# MCU.net
KiCad netlist of a schematic drawn in Altium Designer
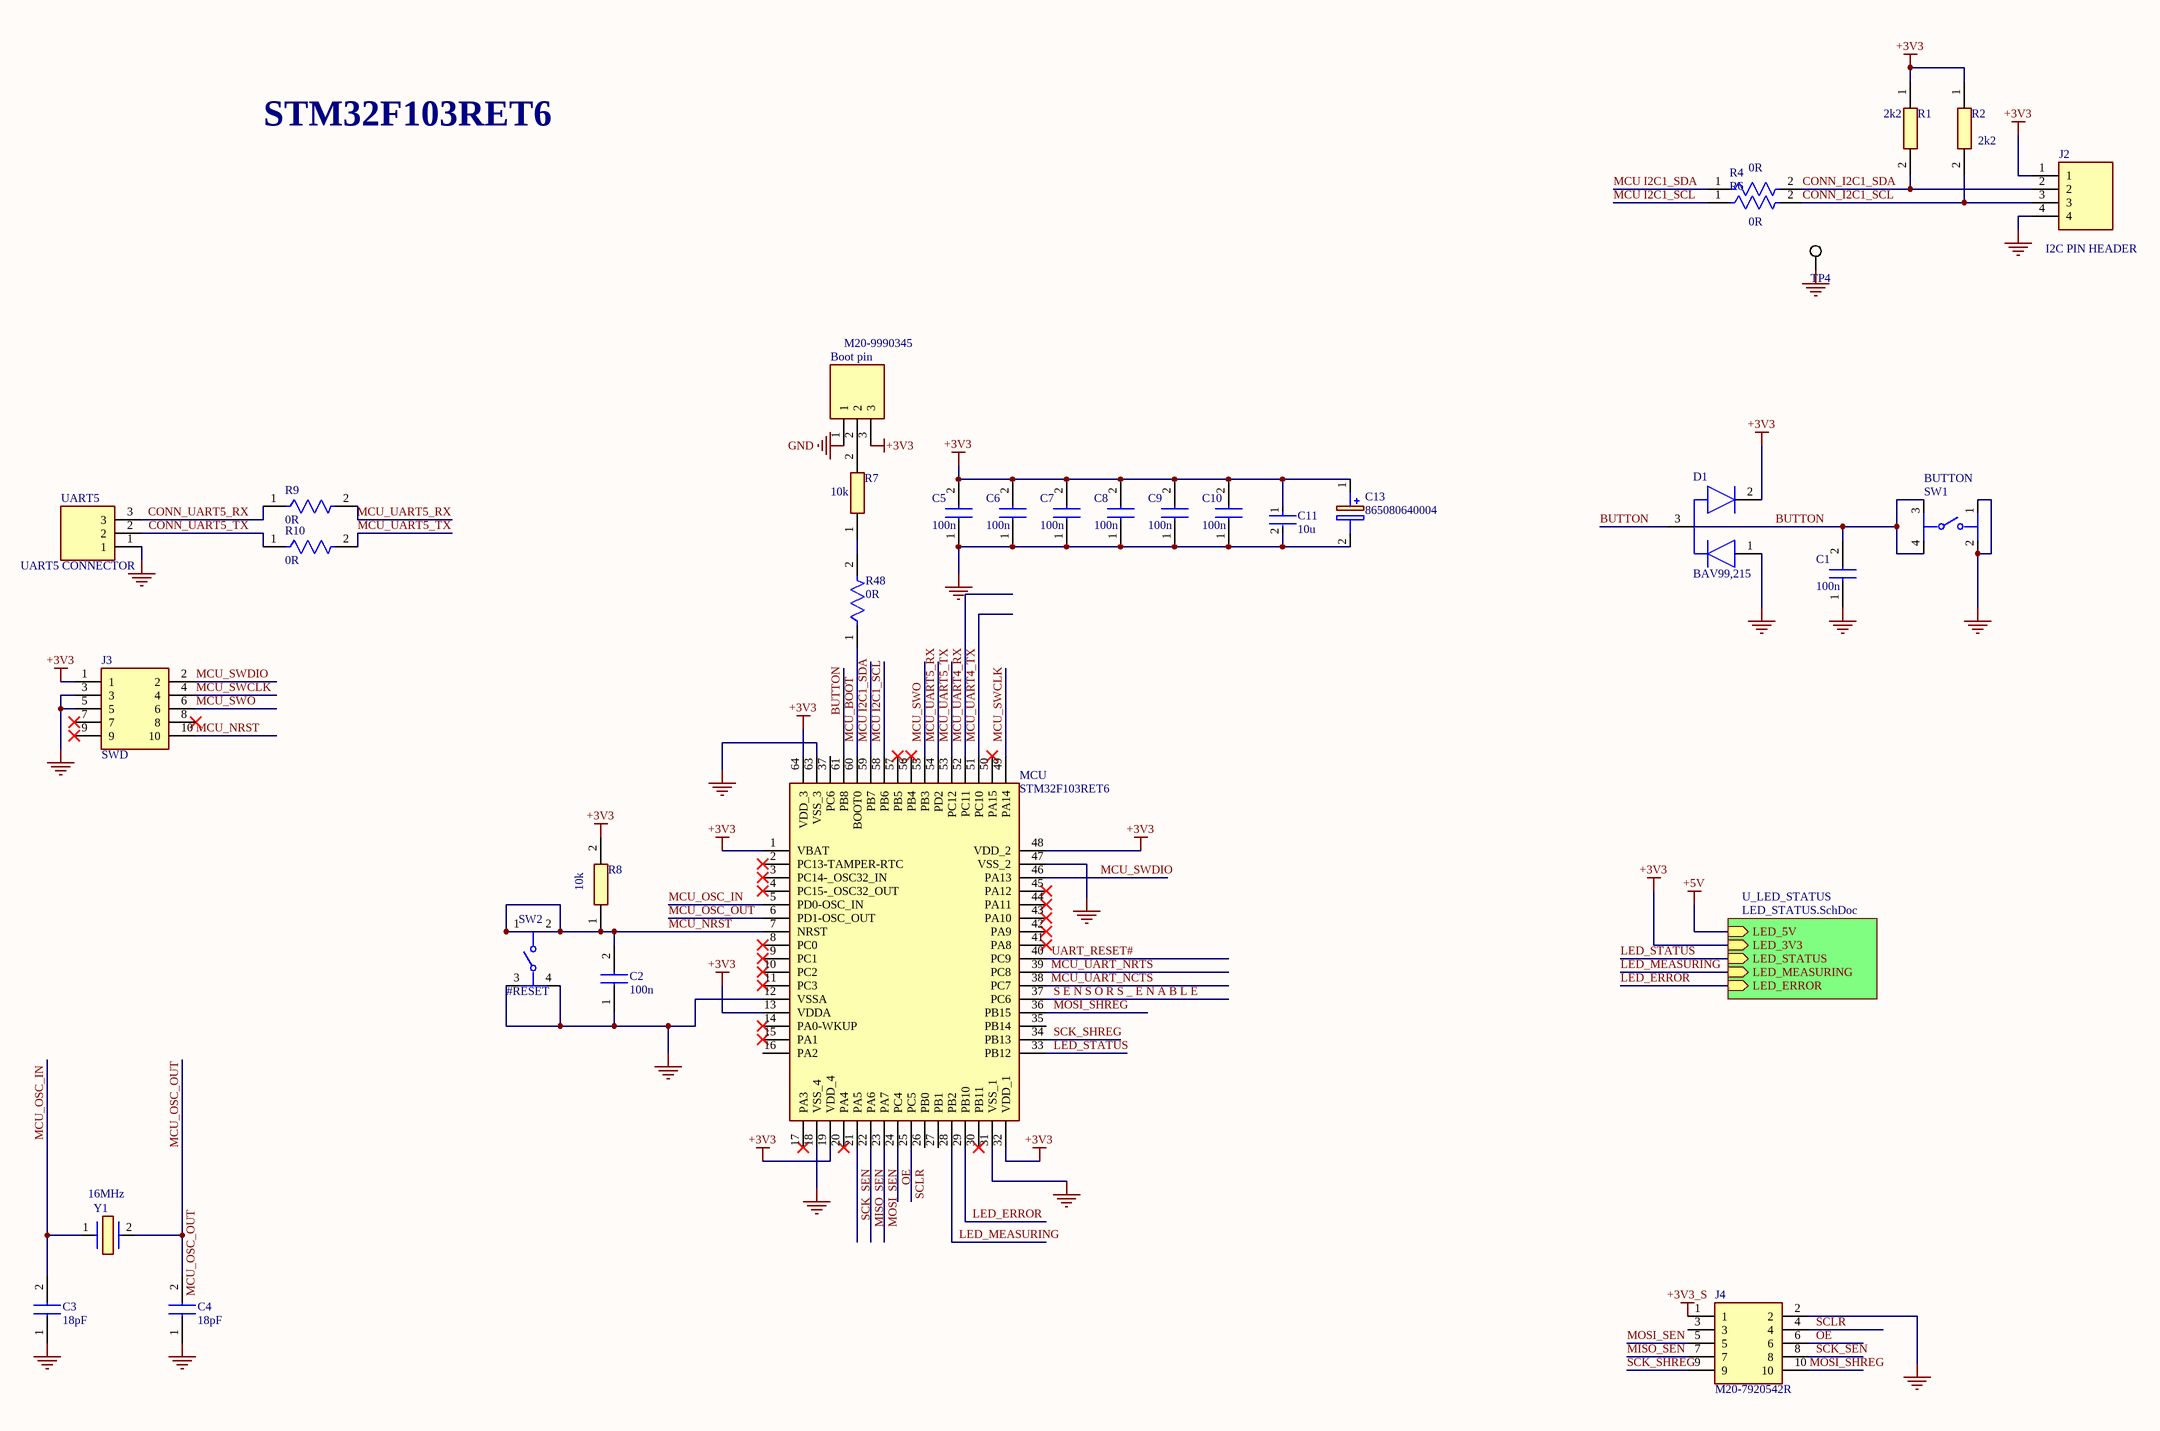
[diagram p0: MCU.SchDoc]

(export (version "E")
  (design (tool "Eeschema 10.0.6"))
  (components
    (comp (ref "Boot pin")
      (value "M20-9990345")
      (footprint "SamacSys:HDRV3W64P0X254_1X3_762X254X864P")
      (description "Connector")
      (fields (field (name "MOUSER PART NUMBER") "855-M20-9990345"))
      (libsource (lib "") (part "M20-9990345_1"))
    )
    (comp (ref "C1")
      (value "100n")
      (footprint "SamacSys:CAPC1608X95N")
      (description "Capacitor")
      (fields
        (field (name "MANUFACTURER_PART_NUMBER") "C0603C104J4RAC")
        (field (name "MOUSER PART NUMBER") "80-C0603C104J4RAC")
      )
      (libsource (lib "SamacSys") (part "C0603C104J4RAC"))
    )
    (comp (ref "C2")
      (value "100n")
      (footprint "SamacSys:CAPC1608X90N")
      (description "Capacitor")
      (fields
        (field (name "MANUFACTURER_PART_NUMBER") "CL10A105KA8NFNC")
        (field (name "MOUSER PART NUMBER") "187-CL10A105KA8NFNC")
      )
      (libsource (lib "*") (part "CL10A105KA8NFNC"))
    )
    (comp (ref "C3")
      (value "18pF")
      (footprint "SamacSys:C0603")
      (description "Capacitor")
      (fields
        (field (name "MANUFACTURER_PART_NUMBER") "C0603C180K4HACTU")
        (field (name "MOUSER PART NUMBER") "80-C0603C180K4HACTU")
      )
      (libsource (lib "*") (part "C0603C180K4HACTU"))
    )
    (comp (ref "C4")
      (value "18pF")
      (footprint "SamacSys:C0603")
      (description "Capacitor")
      (fields
        (field (name "MANUFACTURER_PART_NUMBER") "C0603C180K4HACTU")
        (field (name "MOUSER PART NUMBER") "80-C0603C180K4HACTU")
      )
      (libsource (lib "*") (part "C0603C180K4HACTU"))
    )
    (comp (ref "C5")
      (value "100n")
      (footprint "SamacSys:CAPC1608X95N")
      (description "Capacitor")
      (fields
        (field (name "MANUFACTURER_PART_NUMBER") "C0603C104J4RAC")
        (field (name "MOUSER PART NUMBER") "80-C0603C104J4RAC")
      )
      (libsource (lib "SamacSys") (part "C0603C104J4RAC"))
    )
    (comp (ref "C6")
      (value "100n")
      (footprint "SamacSys:CAPC1608X95N")
      (description "Capacitor")
      (fields
        (field (name "MANUFACTURER_PART_NUMBER") "C0603C104J4RAC")
        (field (name "MOUSER PART NUMBER") "80-C0603C104J4RAC")
      )
      (libsource (lib "SamacSys") (part "C0603C104J4RAC"))
    )
    (comp (ref "C7")
      (value "100n")
      (footprint "SamacSys:CAPC1608X95N")
      (description "Capacitor")
      (fields
        (field (name "MANUFACTURER_PART_NUMBER") "C0603C104J4RAC")
        (field (name "MOUSER PART NUMBER") "80-C0603C104J4RAC")
      )
      (libsource (lib "SamacSys") (part "C0603C104J4RAC"))
    )
    (comp (ref "C8")
      (value "100n")
      (footprint "SamacSys:CAPC1608X95N")
      (description "Capacitor")
      (fields
        (field (name "MANUFACTURER_PART_NUMBER") "C0603C104J4RAC")
        (field (name "MOUSER PART NUMBER") "80-C0603C104J4RAC")
      )
      (libsource (lib "SamacSys") (part "C0603C104J4RAC"))
    )
    (comp (ref "C9")
      (value "100n")
      (footprint "SamacSys:CAPC1608X95N")
      (description "Capacitor")
      (fields
        (field (name "MANUFACTURER_PART_NUMBER") "C0603C104J4RAC")
        (field (name "MOUSER PART NUMBER") "80-C0603C104J4RAC")
      )
      (libsource (lib "SamacSys") (part "C0603C104J4RAC"))
    )
    (comp (ref "C10")
      (value "100n")
      (footprint "SamacSys:CAPC1608X95N")
      (description "Capacitor")
      (fields
        (field (name "MANUFACTURER_PART_NUMBER") "C0603C104J4RAC")
        (field (name "MOUSER PART NUMBER") "80-C0603C104J4RAC")
      )
      (libsource (lib "SamacSys") (part "C0603C104J4RAC"))
    )
    (comp (ref "C11")
      (value "10u")
      (footprint "FP-GRM188-0_2-IPC_A")
      (description "Chip Multilayer Ceramic Capacitors for General Purpose, 0603, 10uF, X5R, 15%, 20%, 16V")
      (fields (field (name "TOLERANCE") "20%") (field (name "VOLTAGE") "16V"))
      (libsource (lib "Altium Content Vault") (part "11868f565c42a9108669ba33697ecf6"))
    )
    (comp (ref "C13")
      (value "865080640004")
      (footprint "SamacSys:865080640004")
      (description "Capacitor Polarised")
      (fields (field (name "MOUSER PART NUMBER") "710-865080640004"))
      (libsource (lib "SamacSys") (part "865080640004"))
    )
    (comp (ref "D1")
      (value "BAV99,215")
      (footprint "SamacSys:BAV99215")
      (description "Diode")
      (fields (field (name "MOUSER PART NUMBER") "771-BAV99-T/R"))
      (libsource (lib "*") (part "BAV99,215"))
    )
    (comp (ref "J2")
      (value "I2C PIN HEADER")
      (footprint "SamacSys:HDRV4W90P0X254_1X4_994X249X560P")
      (description "Connector")
      (fields
        (field (name "MANUFACTURER_PART_NUMBER") "90120-0764")
        (field (name "MOUSER PART NUMBER") "538-90120-0764")
      )
      (libsource (lib "SamacSys") (part "90120-0764"))
    )
    (comp (ref "J3")
      (value "SWD")
      (footprint "SamacSys:HDRV10W64P254_2X5_1270X508X834P")
      (description "Connector")
      (fields
        (field (name "MANUFACTURER_PART_NUMBER") "M20-9760542")
        (field (name "MOUSER PART NUMBER") "855-M20-9760542")
      )
      (libsource (lib "SamacSys") (part "M20-9760542"))
    )
    (comp (ref "J4")
      (value "M20-7920542R")
      (footprint "SamacSys:M207920542R")
      (description "Connector")
      (fields (field (name "MOUSER PART NUMBER") "855-M20-7920542R"))
      (libsource (lib "SamacSys") (part "M20-7920542R"))
    )
    (comp (ref "MCU")
      (value "STM32F103RET6")
      (footprint "SamacSys:QFP50P1200X1200X160-64N")
      (description "Integrated Circuit")
      (fields (field (name "MOUSER PART NUMBER") "511-STM32F103RET6"))
      (libsource (lib "*") (part "STM32F103RET6"))
    )
    (comp (ref "R1")
      (value "2k2")
      (footprint "SamacSys:RESC1608X55N")
      (description "Resistor")
      (fields
        (field (name "MANUFACTURER_PART_NUMBER") "RK73B1JTTD103J")
        (field (name "MOUSER PART NUMBER") "660-RK73B1JTTD103J")
      )
      (libsource (lib "") (part "RK73B1JTTD103J_1"))
    )
    (comp (ref "R2")
      (value "2k2")
      (footprint "SamacSys:RESC1608X55N")
      (description "Resistor")
      (fields
        (field (name "MANUFACTURER_PART_NUMBER") "RK73B1JTTD103J")
        (field (name "MOUSER PART NUMBER") "660-RK73B1JTTD103J")
      )
      (libsource (lib "") (part "RK73B1JTTD103J_1"))
    )
    (comp (ref "R4")
      (value "0R")
      (footprint "FP-ERJ-3GEY0R00V-MFG")
      (description "RES SMD 0 OHM JUMPER 1/10W 0603")
      (fields (field (name "TOLERANCE") "5%") (field (name "MANUFACTURER PART NUMBER") "ERJ-3GEY0R00V"))
      (libsource (lib "Altium Content Vault") (part "1029c3af85768c4190bb7ad29bc67b5"))
    )
    (comp (ref "R6")
      (value "0R")
      (footprint "FP-ERJ-3GEY0R00V-MFG")
      (description "RES SMD 0 OHM JUMPER 1/10W 0603")
      (fields (field (name "TOLERANCE") "5%") (field (name "MANUFACTURER PART NUMBER") "ERJ-3GEY0R00V"))
      (libsource (lib "Altium Content Vault") (part "1029c3af85768c4190bb7ad29bc67b5"))
    )
    (comp (ref "R7")
      (value "10k")
      (footprint "SamacSys:RESC1608X55N")
      (description "Resistor")
      (fields
        (field (name "MANUFACTURER_PART_NUMBER") "RK73B1JTTD103J")
        (field (name "MOUSER PART NUMBER") "660-RK73B1JTTD103J")
      )
      (libsource (lib "*") (part "RK73B1JTTD103J"))
    )
    (comp (ref "R8")
      (value "10k")
      (footprint "SamacSys:RESC1608X55N")
      (description "Resistor")
      (fields
        (field (name "MANUFACTURER_PART_NUMBER") "RK73B1JTTD103J")
        (field (name "MOUSER PART NUMBER") "660-RK73B1JTTD103J")
      )
      (libsource (lib "*") (part "RK73B1JTTD103J"))
    )
    (comp (ref "R9")
      (value "0R")
      (footprint "FP-ERJ-3GEY0R00V-MFG")
      (description "RES SMD 0 OHM JUMPER 1/10W 0603")
      (fields (field (name "TOLERANCE") "5%") (field (name "MANUFACTURER PART NUMBER") "ERJ-3GEY0R00V"))
      (libsource (lib "Altium Content Vault") (part "1029c3af85768c4190bb7ad29bc67b5"))
    )
    (comp (ref "R10")
      (value "0R")
      (footprint "FP-ERJ-3GEY0R00V-MFG")
      (description "RES SMD 0 OHM JUMPER 1/10W 0603")
      (fields (field (name "TOLERANCE") "5%") (field (name "MANUFACTURER PART NUMBER") "ERJ-3GEY0R00V"))
      (libsource (lib "Altium Content Vault") (part "1029c3af85768c4190bb7ad29bc67b5"))
    )
    (comp (ref "R48")
      (value "0R")
      (footprint "FP-ERJ-3GEY0R00V-MFG")
      (description "RES SMD 0 OHM JUMPER 1/10W 0603")
      (fields (field (name "TOLERANCE") "5%") (field (name "MANUFACTURER PART NUMBER") "ERJ-3GEY0R00V"))
      (libsource (lib "Altium Content Vault") (part "1029c3af85768c4190bb7ad29bc67b5"))
    )
    (comp (ref "SW1")
      (value "BUTTON")
      (footprint "FP-PTS645SM43SMTR92LFS-MFG")
      (description "SWITCH TACTILE SPST-NO 0.05A 12V")
      (libsource (lib "Altium Content Vault") (part "1adf0dd01260c80cf25a44bfd6b99ba"))
    )
    (comp (ref "SW2")
      (value "#RESET")
      (footprint "FP-PTS645SM43SMTR92LFS-MFG")
      (description "SWITCH TACTILE SPST-NO 0.05A 12V")
      (libsource (lib "Altium Content Vault") (part "1adf0dd01260c80cf25a44bfd6b99ba"))
    )
    (comp (ref "TP4")
      (value "5019")
      (footprint "KSTN-5019_V")
      (description "Test Point, 1 Position SMD, RoHS, Tape and Reel")
      (libsource (lib "Altium Content Vault") (part "TESTPOINT_WHITE"))
    )
    (comp (ref "UART5")
      (value "UART5 CONNECTOR")
      (footprint "SamacSys:HDRV3W64P0X254_1X3_762X254X864P")
      (description "Connector")
      (fields
        (field (name "MANUFACTURER_PART_NUMBER") "M20-9990345")
        (field (name "MOUSER PART NUMBER") "855-M20-9990345")
      )
      (libsource (lib "SamacSys") (part "M20-9990345"))
    )
    (comp (ref "Y1")
      (value "16MHz")
      (footprint "SamacSys:ABLS")
      (description "Crystal or Oscillator")
      (fields
        (field (name "MANUFACTURER_PART_NUMBER") "ABLS-16.000MHZ-B2-T")
        (field (name "MOUSER PART NUMBER") "815-ABLS-16-B2")
      )
      (libsource (lib "SamacSys") (part "ABLS-16.000MHZ-B2-T"))
    )
  )
  (nets
    (net (code "1") (name "+3V3") (class "Default")
      (node (ref "Boot pin") (pin "3") (pinfunction "3_3") (pintype "passive"))
      (node (ref "C10") (pin "2") (pinfunction "2_2") (pintype "passive"))
      (node (ref "C11") (pin "1") (pinfunction "1_1") (pintype "passive"))
      (node (ref "C13") (pin "1") (pinfunction "+_1") (pintype "passive"))
      (node (ref "C5") (pin "2") (pinfunction "2_2") (pintype "passive"))
      (node (ref "C6") (pin "2") (pinfunction "2_2") (pintype "passive"))
      (node (ref "C7") (pin "2") (pinfunction "2_2") (pintype "passive"))
      (node (ref "C8") (pin "2") (pinfunction "2_2") (pintype "passive"))
      (node (ref "C9") (pin "2") (pinfunction "2_2") (pintype "passive"))
      (node (ref "D1") (pin "2") (pinfunction "E_2") (pintype "passive"))
      (node (ref "J2") (pin "1") (pinfunction "1_1") (pintype "passive"))
      (node (ref "J3") (pin "1") (pinfunction "1_1") (pintype "passive"))
      (node (ref "MCU") (pin "1") (pinfunction "VBAT_1") (pintype "passive"))
      (node (ref "MCU") (pin "13") (pinfunction "VDDA_13") (pintype "passive"))
      (node (ref "MCU") (pin "19") (pinfunction "VDD_4_19") (pintype "passive"))
      (node (ref "MCU") (pin "32") (pinfunction "VDD_1_32") (pintype "passive"))
      (node (ref "MCU") (pin "48") (pinfunction "VDD_2_48") (pintype "passive"))
      (node (ref "MCU") (pin "64") (pinfunction "VDD_3_64") (pintype "passive"))
      (node (ref "R1") (pin "1") (pinfunction "1_1") (pintype "passive"))
      (node (ref "R2") (pin "1") (pinfunction "1_1") (pintype "passive"))
      (node (ref "R8") (pin "2") (pinfunction "2_2") (pintype "passive"))
    )
    (net (code "2") (name "+3V3_S") (class "Default")
      (node (ref "J4") (pin "1") (pinfunction "1_1") (pintype "passive"))
    )
    (net (code "4") (name "/BUTTON") (class "Default")
      (node (ref "C1") (pin "2") (pinfunction "2_2") (pintype "passive"))
      (node (ref "D1") (pin "3") (pinfunction "C_3") (pintype "passive"))
      (node (ref "MCU") (pin "61") (pinfunction "PB8_61") (pintype "passive"))
      (node (ref "SW1") (pin "3") (pinfunction "3_3") (pintype "passive"))
      (node (ref "SW1") (pin "4") (pinfunction "4_4") (pintype "passive"))
    )
    (net (code "5") (name "/CONN_I2C1_SCL") (class "Default")
      (node (ref "J2") (pin "3") (pinfunction "3_3") (pintype "passive"))
      (node (ref "R2") (pin "2") (pinfunction "2_2") (pintype "passive"))
      (node (ref "R6") (pin "2") (pinfunction "2_2") (pintype "passive"))
    )
    (net (code "6") (name "/CONN_I2C1_SDA") (class "Default")
      (node (ref "J2") (pin "2") (pinfunction "2_2") (pintype "passive"))
      (node (ref "R1") (pin "2") (pinfunction "2_2") (pintype "passive"))
      (node (ref "R4") (pin "2") (pinfunction "2_2") (pintype "passive"))
    )
    (net (code "7") (name "/CONN_UART5_RX") (class "Default")
      (node (ref "R9") (pin "1") (pinfunction "1_1") (pintype "passive"))
      (node (ref "UART5") (pin "3") (pinfunction "3_3") (pintype "passive"))
    )
    (net (code "8") (name "/CONN_UART5_TX") (class "Default")
      (node (ref "R10") (pin "1") (pinfunction "1_1") (pintype "passive"))
      (node (ref "UART5") (pin "2") (pinfunction "2_2") (pintype "passive"))
    )
    (net (code "9") (name "/LED_ERROR") (class "Default")
      (node (ref "MCU") (pin "29") (pinfunction "PB10_29") (pintype "passive"))
    )
    (net (code "10") (name "/LED_MEASURING") (class "Default")
      (node (ref "MCU") (pin "28") (pinfunction "PB2_28") (pintype "passive"))
    )
    (net (code "11") (name "/LED_STATUS") (class "Default")
      (node (ref "MCU") (pin "33") (pinfunction "PB12_33") (pintype "passive"))
    )
    (net (code "12") (name "/MCU I2C1_SCL") (class "Default")
      (node (ref "MCU") (pin "58") (pinfunction "PB6_58") (pintype "passive"))
      (node (ref "R6") (pin "1") (pinfunction "1_1") (pintype "passive"))
    )
    (net (code "13") (name "/MCU I2C1_SDA") (class "Default")
      (node (ref "MCU") (pin "59") (pinfunction "PB7_59") (pintype "passive"))
      (node (ref "R4") (pin "1") (pinfunction "1_1") (pintype "passive"))
    )
    (net (code "14") (name "/MCU_BOOT") (class "Default")
      (node (ref "MCU") (pin "60") (pinfunction "BOOT0_60") (pintype "passive"))
      (node (ref "R48") (pin "1") (pinfunction "1_1") (pintype "passive"))
    )
    (net (code "15") (name "/MCU_NRST") (class "Default")
      (node (ref "C2") (pin "2") (pinfunction "2_2") (pintype "passive"))
      (node (ref "J3") (pin "10") (pinfunction "10_10") (pintype "passive"))
      (node (ref "MCU") (pin "7") (pinfunction "NRST_7") (pintype "passive"))
      (node (ref "R8") (pin "1") (pinfunction "1_1") (pintype "passive"))
      (node (ref "SW2") (pin "1") (pinfunction "1_1") (pintype "passive"))
      (node (ref "SW2") (pin "2") (pinfunction "2_2") (pintype "passive"))
    )
    (net (code "16") (name "/MCU_OSC_IN") (class "Default")
      (node (ref "C3") (pin "2") (pinfunction "2_2") (pintype "passive"))
      (node (ref "MCU") (pin "5") (pinfunction "PD0-OSC_IN_5") (pintype "passive"))
      (node (ref "Y1") (pin "1") (pinfunction "1_1") (pintype "passive"))
    )
    (net (code "17") (name "/MCU_OSC_OUT") (class "Default")
      (node (ref "C4") (pin "2") (pinfunction "2_2") (pintype "passive"))
      (node (ref "MCU") (pin "6") (pinfunction "PD1-OSC_OUT_6") (pintype "passive"))
      (node (ref "Y1") (pin "2") (pinfunction "2_2") (pintype "passive"))
    )
    (net (code "18") (name "/MCU_SWCLK") (class "Default")
      (node (ref "J3") (pin "4") (pinfunction "4_4") (pintype "passive"))
      (node (ref "MCU") (pin "49") (pinfunction "PA14_49") (pintype "passive"))
    )
    (net (code "19") (name "/MCU_SWDIO") (class "Default")
      (node (ref "J3") (pin "2") (pinfunction "2_2") (pintype "passive"))
      (node (ref "MCU") (pin "46") (pinfunction "PA13_46") (pintype "passive"))
    )
    (net (code "20") (name "/MCU_SWO") (class "Default")
      (node (ref "J3") (pin "6") (pinfunction "6_6") (pintype "passive"))
      (node (ref "MCU") (pin "55") (pinfunction "PB3_55") (pintype "passive"))
    )
    (net (code "21") (name "/MCU_UART4_RX") (class "Default")
      (node (ref "MCU") (pin "52") (pinfunction "PC11_52") (pintype "passive"))
    )
    (net (code "22") (name "/MCU_UART4_TX") (class "Default")
      (node (ref "MCU") (pin "51") (pinfunction "PC10_51") (pintype "passive"))
    )
    (net (code "23") (name "/MCU_UART5_RX") (class "Default")
      (node (ref "MCU") (pin "54") (pinfunction "PD2_54") (pintype "passive"))
      (node (ref "R9") (pin "2") (pinfunction "2_2") (pintype "passive"))
    )
    (net (code "24") (name "/MCU_UART5_TX") (class "Default")
      (node (ref "MCU") (pin "53") (pinfunction "PC12_53") (pintype "passive"))
      (node (ref "R10") (pin "2") (pinfunction "2_2") (pintype "passive"))
    )
    (net (code "25") (name "/MCU_UART_NCTS") (class "Default")
      (node (ref "MCU") (pin "38") (pinfunction "PC7_38") (pintype "passive"))
    )
    (net (code "26") (name "/MCU_UART_NRTS") (class "Default")
      (node (ref "MCU") (pin "39") (pinfunction "PC8_39") (pintype "passive"))
    )
    (net (code "27") (name "/MISO_SEN") (class "Default")
      (node (ref "J4") (pin "7") (pinfunction "7_7") (pintype "passive"))
      (node (ref "MCU") (pin "22") (pinfunction "PA6_22") (pintype "passive"))
    )
    (net (code "28") (name "/MOSI_SEN") (class "Default")
      (node (ref "J4") (pin "5") (pinfunction "5_5") (pintype "passive"))
      (node (ref "MCU") (pin "23") (pinfunction "PA7_23") (pintype "passive"))
    )
    (net (code "29") (name "/MOSI_SHREG") (class "Default")
      (node (ref "J4") (pin "10") (pinfunction "10_10") (pintype "passive"))
      (node (ref "MCU") (pin "36") (pinfunction "PB15_36") (pintype "passive"))
    )
    (net (code "30") (name "/OE") (class "Default")
      (node (ref "J4") (pin "6") (pinfunction "6_6") (pintype "passive"))
      (node (ref "MCU") (pin "24") (pinfunction "PC4_24") (pintype "passive"))
    )
    (net (code "31") (name "/SCK_SEN") (class "Default")
      (node (ref "J4") (pin "8") (pinfunction "8_8") (pintype "passive"))
      (node (ref "MCU") (pin "21") (pinfunction "PA5_21") (pintype "passive"))
    )
    (net (code "32") (name "/SCK_SHREG") (class "Default")
      (node (ref "J4") (pin "9") (pinfunction "9_9") (pintype "passive"))
      (node (ref "MCU") (pin "34") (pinfunction "PB13_34") (pintype "passive"))
    )
    (net (code "33") (name "/SCLR") (class "Default")
      (node (ref "J4") (pin "4") (pinfunction "4_4") (pintype "passive"))
      (node (ref "MCU") (pin "25") (pinfunction "PC5_25") (pintype "passive"))
    )
    (net (code "34") (name "/UART_RESET#") (class "Default")
      (node (ref "MCU") (pin "40") (pinfunction "PC9_40") (pintype "passive"))
    )
    (net (code "35") (name "/~{S} ~{E} ~{N} ~{S} ~{O} ~{R} ~{S} ~{_} ~{E} ~{N} ~{A} ~{B} ~{L} ~{E}") (class "Default")
      (node (ref "MCU") (pin "37") (pinfunction "PC6_37") (pintype "passive"))
    )
    (net (code "36") (name "GND") (class "Default")
      (node (ref "Boot pin") (pin "1") (pinfunction "1_1") (pintype "passive"))
      (node (ref "C1") (pin "1") (pinfunction "1_1") (pintype "passive"))
      (node (ref "C10") (pin "1") (pinfunction "1_1") (pintype "passive"))
      (node (ref "C11") (pin "2") (pinfunction "2_2") (pintype "passive"))
      (node (ref "C13") (pin "2") (pinfunction "-_2") (pintype "passive"))
      (node (ref "C2") (pin "1") (pinfunction "1_1") (pintype "passive"))
      (node (ref "C3") (pin "1") (pinfunction "1_1") (pintype "passive"))
      (node (ref "C4") (pin "1") (pinfunction "1_1") (pintype "passive"))
      (node (ref "C5") (pin "1") (pinfunction "1_1") (pintype "passive"))
      (node (ref "C6") (pin "1") (pinfunction "1_1") (pintype "passive"))
      (node (ref "C7") (pin "1") (pinfunction "1_1") (pintype "passive"))
      (node (ref "C8") (pin "1") (pinfunction "1_1") (pintype "passive"))
      (node (ref "C9") (pin "1") (pinfunction "1_1") (pintype "passive"))
      (node (ref "D1") (pin "1") (pinfunction "B_1") (pintype "passive"))
      (node (ref "J2") (pin "4") (pinfunction "4_4") (pintype "passive"))
      (node (ref "J3") (pin "3") (pinfunction "3_3") (pintype "passive"))
      (node (ref "J3") (pin "5") (pinfunction "5_5") (pintype "passive"))
      (node (ref "J4") (pin "2") (pinfunction "2_2") (pintype "passive"))
      (node (ref "MCU") (pin "12") (pinfunction "VSSA_12") (pintype "passive"))
      (node (ref "MCU") (pin "18") (pinfunction "VSS_4_18") (pintype "passive"))
      (node (ref "MCU") (pin "31") (pinfunction "VSS_1_31") (pintype "passive"))
      (node (ref "MCU") (pin "47") (pinfunction "VSS_2_47") (pintype "passive"))
      (node (ref "MCU") (pin "63") (pinfunction "VSS_3_63") (pintype "passive"))
      (node (ref "SW1") (pin "1") (pinfunction "1_1") (pintype "passive"))
      (node (ref "SW1") (pin "2") (pinfunction "2_2") (pintype "passive"))
      (node (ref "SW2") (pin "3") (pinfunction "3_3") (pintype "passive"))
      (node (ref "SW2") (pin "4") (pinfunction "4_4") (pintype "passive"))
      (node (ref "TP4") (pin "1") (pinfunction "1_1") (pintype "passive"))
      (node (ref "UART5") (pin "1") (pinfunction "1_1") (pintype "passive"))
    )
    (net (code "37") (name "Net-(Boot pin-Pad2)") (class "Default")
      (node (ref "Boot pin") (pin "2") (pinfunction "2_2") (pintype "passive"))
      (node (ref "R7") (pin "2") (pinfunction "2_2") (pintype "passive"))
    )
    (net (code "38") (name "Net-(R48-Pad2)") (class "Default")
      (node (ref "R48") (pin "2") (pinfunction "2_2") (pintype "passive"))
      (node (ref "R7") (pin "1") (pinfunction "1_1") (pintype "passive"))
    )
    (net (code "39") (name "unconnected-(J3-Pad7)") (class "Default")
      (node (ref "J3") (pin "7") (pinfunction "7_7") (pintype "passive+no_connect"))
    )
    (net (code "40") (name "unconnected-(J3-Pad8)") (class "Default")
      (node (ref "J3") (pin "8") (pinfunction "8_8") (pintype "passive+no_connect"))
    )
    (net (code "41") (name "unconnected-(J3-Pad9)") (class "Default")
      (node (ref "J3") (pin "9") (pinfunction "9_9") (pintype "passive+no_connect"))
    )
    (net (code "42") (name "unconnected-(J4-Pad3)") (class "Default")
      (node (ref "J4") (pin "3") (pinfunction "3_3") (pintype "passive"))
    )
    (net (code "43") (name "unconnected-(MCU-PA0-WKUP-Pad14)") (class "Default")
      (node (ref "MCU") (pin "14") (pinfunction "PA0-WKUP_14") (pintype "passive+no_connect"))
    )
    (net (code "44") (name "unconnected-(MCU-PA1-Pad15)") (class "Default")
      (node (ref "MCU") (pin "15") (pinfunction "PA1_15") (pintype "passive+no_connect"))
    )
    (net (code "45") (name "unconnected-(MCU-PA2-Pad16)") (class "Default")
      (node (ref "MCU") (pin "16") (pinfunction "PA2_16") (pintype "passive"))
    )
    (net (code "46") (name "unconnected-(MCU-PA3-Pad17)") (class "Default")
      (node (ref "MCU") (pin "17") (pinfunction "PA3_17") (pintype "passive+no_connect"))
    )
    (net (code "47") (name "unconnected-(MCU-PA4-Pad20)") (class "Default")
      (node (ref "MCU") (pin "20") (pinfunction "PA4_20") (pintype "passive+no_connect"))
    )
    (net (code "48") (name "unconnected-(MCU-PA8-Pad41)") (class "Default")
      (node (ref "MCU") (pin "41") (pinfunction "PA8_41") (pintype "passive+no_connect"))
    )
    (net (code "49") (name "unconnected-(MCU-PA9-Pad42)") (class "Default")
      (node (ref "MCU") (pin "42") (pinfunction "PA9_42") (pintype "passive+no_connect"))
    )
    (net (code "50") (name "unconnected-(MCU-PA10-Pad43)") (class "Default")
      (node (ref "MCU") (pin "43") (pinfunction "PA10_43") (pintype "passive+no_connect"))
    )
    (net (code "51") (name "unconnected-(MCU-PA11-Pad44)") (class "Default")
      (node (ref "MCU") (pin "44") (pinfunction "PA11_44") (pintype "passive+no_connect"))
    )
    (net (code "52") (name "unconnected-(MCU-PA12-Pad45)") (class "Default")
      (node (ref "MCU") (pin "45") (pinfunction "PA12_45") (pintype "passive+no_connect"))
    )
    (net (code "53") (name "unconnected-(MCU-PA15-Pad50)") (class "Default")
      (node (ref "MCU") (pin "50") (pinfunction "PA15_50") (pintype "passive+no_connect"))
    )
    (net (code "54") (name "unconnected-(MCU-PB0-Pad26)") (class "Default")
      (node (ref "MCU") (pin "26") (pinfunction "PB0_26") (pintype "passive"))
    )
    (net (code "55") (name "unconnected-(MCU-PB1-Pad27)") (class "Default")
      (node (ref "MCU") (pin "27") (pinfunction "PB1_27") (pintype "passive"))
    )
    (net (code "56") (name "unconnected-(MCU-PB4-Pad56)") (class "Default")
      (node (ref "MCU") (pin "56") (pinfunction "PB4_56") (pintype "passive+no_connect"))
    )
    (net (code "57") (name "unconnected-(MCU-PB5-Pad57)") (class "Default")
      (node (ref "MCU") (pin "57") (pinfunction "PB5_57") (pintype "passive+no_connect"))
    )
    (net (code "58") (name "unconnected-(MCU-PB11-Pad30)") (class "Default")
      (node (ref "MCU") (pin "30") (pinfunction "PB11_30") (pintype "passive+no_connect"))
    )
    (net (code "59") (name "unconnected-(MCU-PB14-Pad35)") (class "Default")
      (node (ref "MCU") (pin "35") (pinfunction "PB14_35") (pintype "passive"))
    )
    (net (code "60") (name "unconnected-(MCU-PC0-Pad8)") (class "Default")
      (node (ref "MCU") (pin "8") (pinfunction "PC0_8") (pintype "passive+no_connect"))
    )
    (net (code "61") (name "unconnected-(MCU-PC1-Pad9)") (class "Default")
      (node (ref "MCU") (pin "9") (pinfunction "PC1_9") (pintype "passive+no_connect"))
    )
    (net (code "62") (name "unconnected-(MCU-PC2-Pad10)") (class "Default")
      (node (ref "MCU") (pin "10") (pinfunction "PC2_10") (pintype "passive+no_connect"))
    )
    (net (code "63") (name "unconnected-(MCU-PC3-Pad11)") (class "Default")
      (node (ref "MCU") (pin "11") (pinfunction "PC3_11") (pintype "passive+no_connect"))
    )
    (net (code "64") (name "unconnected-(MCU-PC6-Pad37)") (class "Default")
      (node (ref "MCU") (pin "37") (pinfunction "PC6_37") (pintype "passive"))
    )
    (net (code "65") (name "unconnected-(MCU-PC13-TAMPER-RTC-Pad2)") (class "Default")
      (node (ref "MCU") (pin "2") (pinfunction "PC13-TAMPER-RTC_2") (pintype "passive+no_connect"))
    )
    (net (code "66") (name "unconnected-(MCU-PC14-_OSC32_IN-Pad3)") (class "Default")
      (node (ref "MCU") (pin "3") (pinfunction "PC14-_OSC32_IN_3") (pintype "passive+no_connect"))
    )
    (net (code "67") (name "unconnected-(MCU-PC15-_OSC32_OUT-Pad4)") (class "Default")
      (node (ref "MCU") (pin "4") (pinfunction "PC15-_OSC32_OUT_4") (pintype "passive+no_connect"))
    )
  )
)
